# contra1567.net
KiCad netlist of a schematic drawn in EAGLE
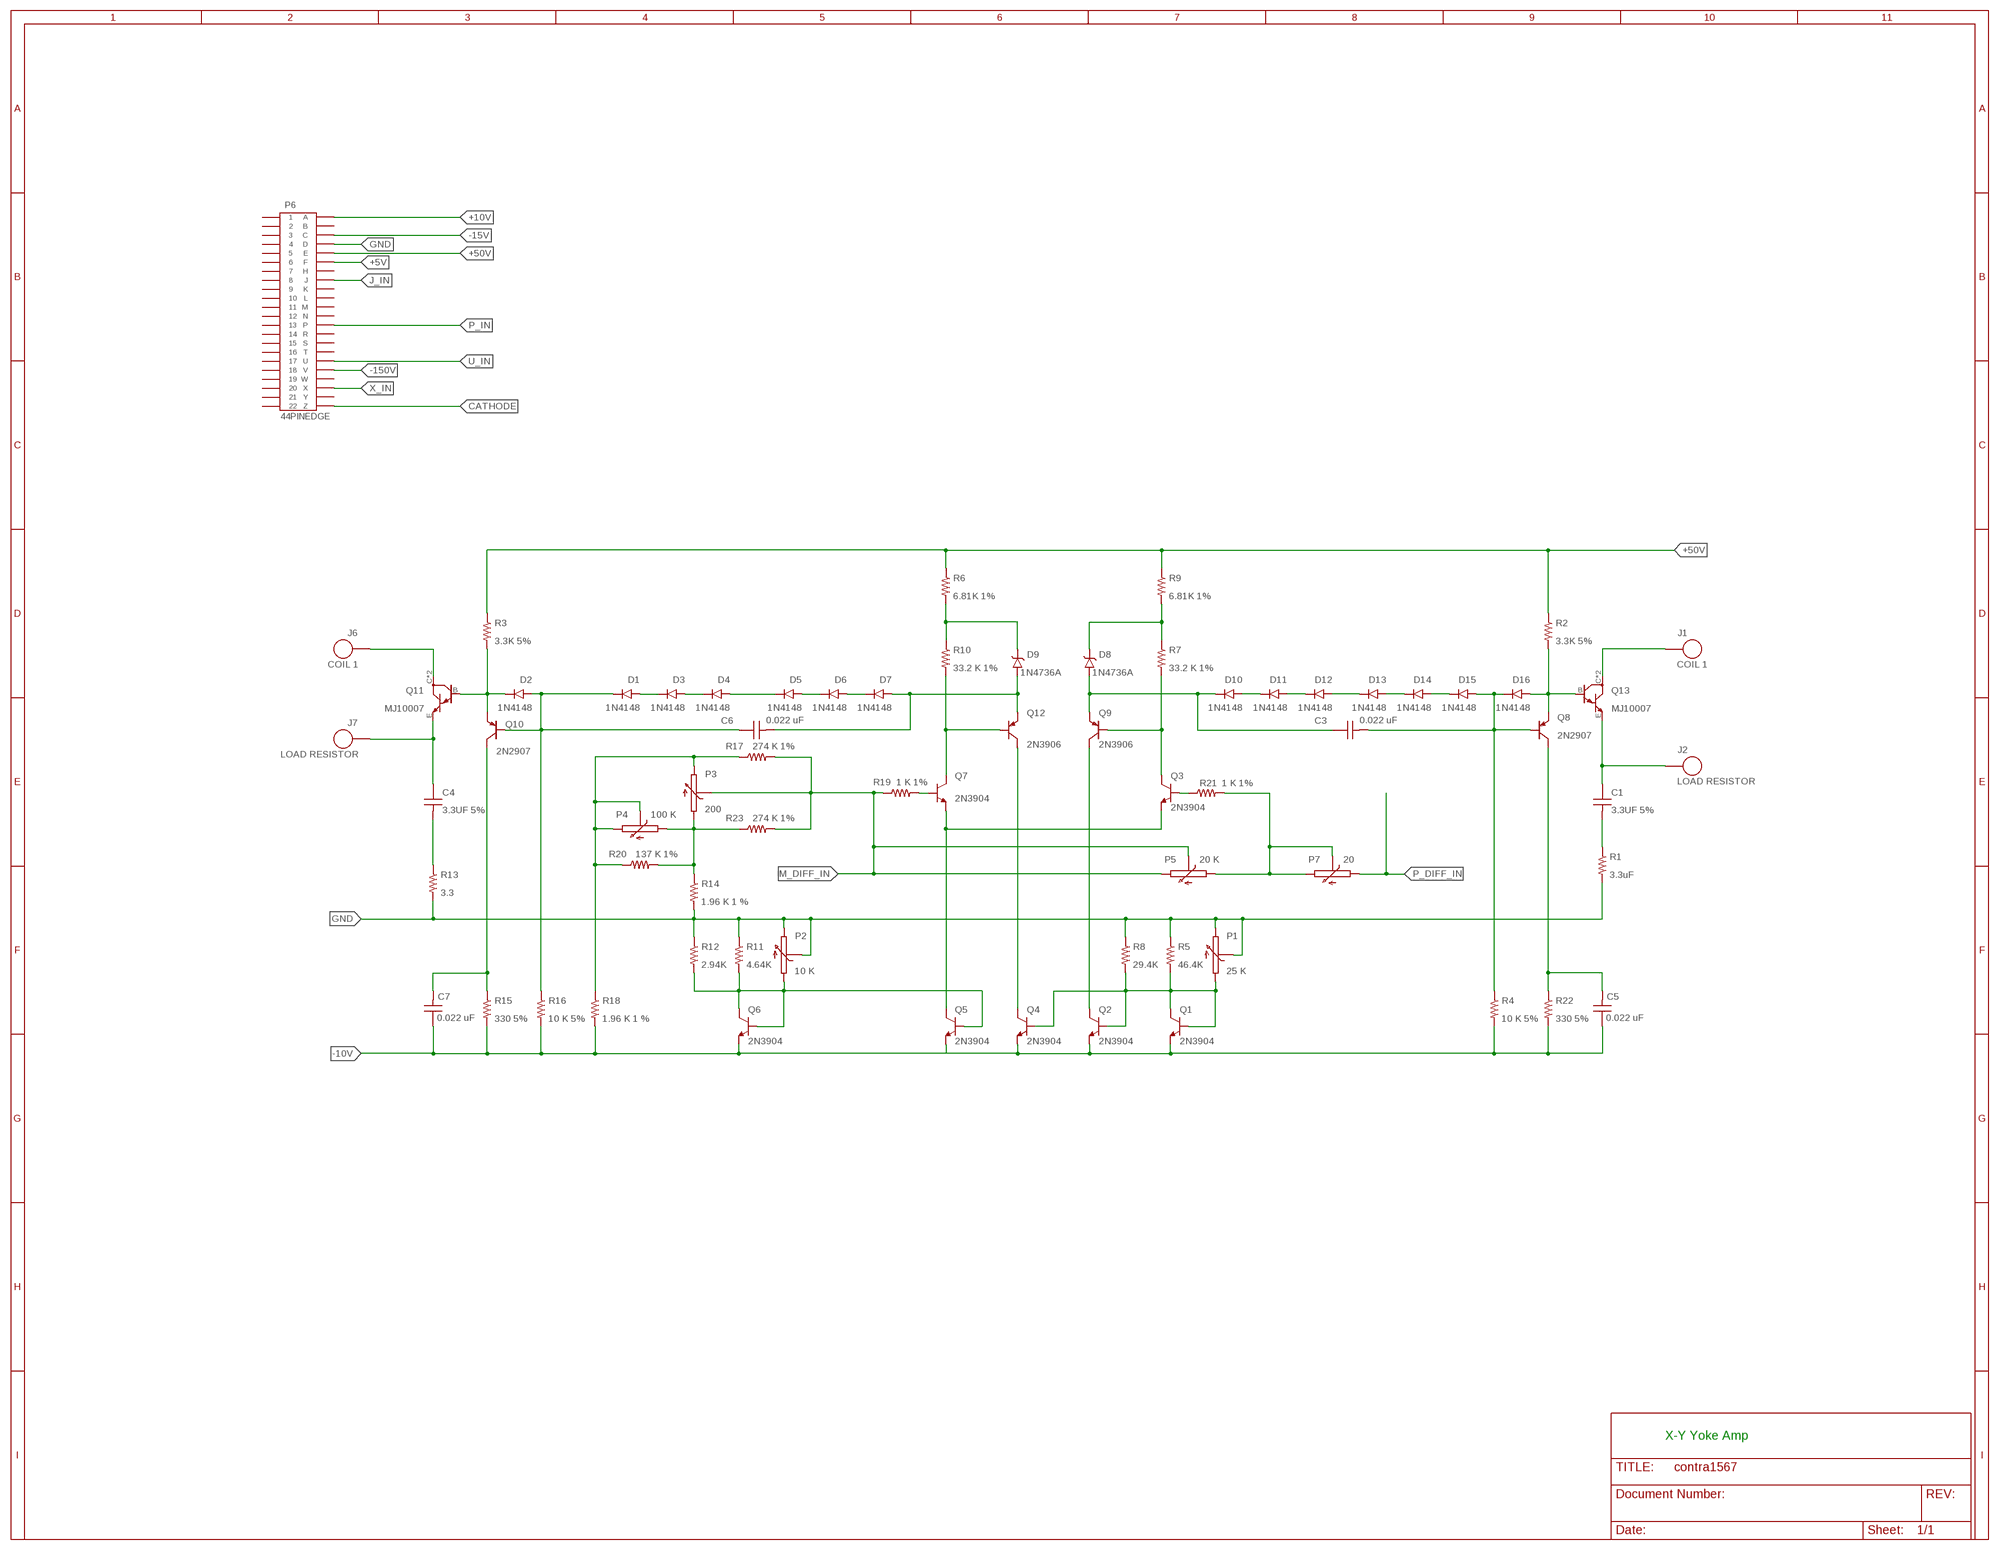
[diagram p0: schematic, sheet 1]

(export (version "E")
  (design (tool "Eeschema 10.0.6"))
  (components
    (comp (ref "C1")
      (value "3.3UF 5%")
      (footprint "eagle-import:CAP-3-PT-ZERO-3UF-250V-FILM")
      (libsource (lib "eagle-import") (part "ECQ-E2335JF"))
    )
    (comp (ref "C3")
      (value "0.022 uF")
      (footprint "eagle-import:CAP-ZERO-PT-ZERO-22UF-250V-FILM")
      (libsource (lib "eagle-import") (part "ECQ-E2223JF"))
    )
    (comp (ref "C4")
      (value "3.3UF 5%")
      (footprint "eagle-import:CAP-3-PT-ZERO-3UF-250V-FILM")
      (libsource (lib "eagle-import") (part "ECQ-E2335JF"))
    )
    (comp (ref "C5")
      (value "0.022 uF")
      (footprint "eagle-import:CAP-ZERO-PT-ZERO-22UF-250V-FILM")
      (libsource (lib "eagle-import") (part "ECQ-E2223JF"))
    )
    (comp (ref "C6")
      (value "0.022 uF")
      (footprint "eagle-import:CAP-ZERO-PT-ZERO-22UF-250V-FILM")
      (libsource (lib "eagle-import") (part "ECQ-E2223JF"))
    )
    (comp (ref "C7")
      (value "0.022 uF")
      (footprint "eagle-import:CAP-ZERO-PT-ZERO-22UF-250V-FILM")
      (libsource (lib "eagle-import") (part "ECQ-E2223JF"))
    )
    (comp (ref "D1")
      (value "1N4148")
      (footprint "eagle-import:DO35-7")
      (libsource (lib "eagle-import") (part "1N4148"))
    )
    (comp (ref "D2")
      (value "1N4148")
      (footprint "eagle-import:DO35-7")
      (libsource (lib "eagle-import") (part "1N4148"))
    )
    (comp (ref "D3")
      (value "1N4148")
      (footprint "eagle-import:DO35-7")
      (libsource (lib "eagle-import") (part "1N4148"))
    )
    (comp (ref "D4")
      (value "1N4148")
      (footprint "eagle-import:DO35-7")
      (libsource (lib "eagle-import") (part "1N4148"))
    )
    (comp (ref "D5")
      (value "1N4148")
      (footprint "eagle-import:DO35-7")
      (libsource (lib "eagle-import") (part "1N4148"))
    )
    (comp (ref "D6")
      (value "1N4148")
      (footprint "eagle-import:DO35-7")
      (libsource (lib "eagle-import") (part "1N4148"))
    )
    (comp (ref "D7")
      (value "1N4148")
      (footprint "eagle-import:DO35-7")
      (libsource (lib "eagle-import") (part "1N4148"))
    )
    (comp (ref "D8")
      (value "1N4736A")
      (footprint "eagle-import:DO41")
      (libsource (lib "eagle-import") (part "1N4736A"))
    )
    (comp (ref "D9")
      (value "1N4736A")
      (footprint "eagle-import:DO41")
      (libsource (lib "eagle-import") (part "1N4736A"))
    )
    (comp (ref "D10")
      (value "1N4148")
      (footprint "eagle-import:DO35-7")
      (libsource (lib "eagle-import") (part "1N4148"))
    )
    (comp (ref "D11")
      (value "1N4148")
      (footprint "eagle-import:DO35-7")
      (libsource (lib "eagle-import") (part "1N4148"))
    )
    (comp (ref "D12")
      (value "1N4148")
      (footprint "eagle-import:DO35-7")
      (libsource (lib "eagle-import") (part "1N4148"))
    )
    (comp (ref "D13")
      (value "1N4148")
      (footprint "eagle-import:DO35-7")
      (libsource (lib "eagle-import") (part "1N4148"))
    )
    (comp (ref "D14")
      (value "1N4148")
      (footprint "eagle-import:DO35-7")
      (libsource (lib "eagle-import") (part "1N4148"))
    )
    (comp (ref "D15")
      (value "1N4148")
      (footprint "eagle-import:DO35-7")
      (libsource (lib "eagle-import") (part "1N4148"))
    )
    (comp (ref "D16")
      (value "1N4148")
      (footprint "eagle-import:DO35-7")
      (libsource (lib "eagle-import") (part "1N4148"))
    )
    (comp (ref "J1")
      (value "COIL 1")
      (footprint "eagle-import:AWG18")
      (libsource (lib "eagle-import") (part "AWG18"))
    )
    (comp (ref "J2")
      (value "LOAD RESISTOR")
      (footprint "eagle-import:AWG18")
      (libsource (lib "eagle-import") (part "AWG18"))
    )
    (comp (ref "J6")
      (value "COIL 1")
      (footprint "eagle-import:AWG18")
      (libsource (lib "eagle-import") (part "AWG18"))
    )
    (comp (ref "J7")
      (value "LOAD RESISTOR")
      (footprint "eagle-import:AWG18")
      (libsource (lib "eagle-import") (part "AWG18"))
    )
    (comp (ref "P1")
      (value "25 K")
      (footprint "eagle-import:3006P")
      (libsource (lib "eagle-import") (part "POT-3006P"))
    )
    (comp (ref "P2")
      (value "10 K")
      (footprint "eagle-import:3006P")
      (libsource (lib "eagle-import") (part "POT-3006P"))
    )
    (comp (ref "P3")
      (value "200")
      (footprint "eagle-import:3006P")
      (libsource (lib "eagle-import") (part "POT-3006P"))
    )
    (comp (ref "P4")
      (value "100 K")
      (footprint "eagle-import:3006P")
      (libsource (lib "eagle-import") (part "POT-3006P"))
    )
    (comp (ref "P5")
      (value "20 K")
      (footprint "eagle-import:3006P")
      (libsource (lib "eagle-import") (part "POT-3006P"))
    )
    (comp (ref "P6")
      (value "44PINEDGE")
      (footprint "eagle-import:44PINEDGE")
      (libsource (lib "eagle-import") (part "44PINEDGE"))
    )
    (comp (ref "P7")
      (value "20")
      (footprint "eagle-import:3006P")
      (libsource (lib "eagle-import") (part "POT-3006P"))
    )
    (comp (ref "Q1")
      (value "2N3904")
      (footprint "eagle-import:TO92")
      (libsource (lib "eagle-import") (part "2N3904"))
    )
    (comp (ref "Q2")
      (value "2N3904")
      (footprint "eagle-import:TO92")
      (libsource (lib "eagle-import") (part "2N3904"))
    )
    (comp (ref "Q3")
      (value "2N3904")
      (footprint "eagle-import:TO92")
      (libsource (lib "eagle-import") (part "2N3904"))
    )
    (comp (ref "Q4")
      (value "2N3904")
      (footprint "eagle-import:TO92")
      (libsource (lib "eagle-import") (part "2N3904"))
    )
    (comp (ref "Q5")
      (value "2N3904")
      (footprint "eagle-import:TO92")
      (libsource (lib "eagle-import") (part "2N3904"))
    )
    (comp (ref "Q6")
      (value "2N3904")
      (footprint "eagle-import:TO92")
      (libsource (lib "eagle-import") (part "2N3904"))
    )
    (comp (ref "Q7")
      (value "2N3904")
      (footprint "eagle-import:TO92")
      (libsource (lib "eagle-import") (part "2N3904"))
    )
    (comp (ref "Q8")
      (value "2N2907")
      (footprint "eagle-import:TO18")
      (libsource (lib "eagle-import") (part "2N2907"))
    )
    (comp (ref "Q9")
      (value "2N3906")
      (footprint "eagle-import:TO92")
      (libsource (lib "eagle-import") (part "2N3906"))
    )
    (comp (ref "Q10")
      (value "2N2907")
      (footprint "eagle-import:TO18")
      (libsource (lib "eagle-import") (part "2N2907"))
    )
    (comp (ref "Q11")
      (value "MJ10007")
      (footprint "eagle-import:TO3")
      (libsource (lib "eagle-import") (part "MJ10007"))
    )
    (comp (ref "Q12")
      (value "2N3906")
      (footprint "eagle-import:TO92")
      (libsource (lib "eagle-import") (part "2N3906"))
    )
    (comp (ref "Q13")
      (value "MJ10007")
      (footprint "eagle-import:TO3")
      (libsource (lib "eagle-import") (part "MJ10007"))
    )
    (comp (ref "R1")
      (value "3.3uF")
      (footprint "eagle-import:R_THREEWATT")
      (libsource (lib "eagle-import") (part "AXIALRESISTORTHREE_WATT"))
    )
    (comp (ref "R2")
      (value "3.3K 5%")
      (footprint "eagle-import:R_TWOWATT")
      (libsource (lib "eagle-import") (part "AXIALRESISTORTWO_WATT"))
    )
    (comp (ref "R3")
      (value "3.3K 5%")
      (footprint "eagle-import:R_TWOWATT")
      (libsource (lib "eagle-import") (part "AXIALRESISTORTWO_WATT"))
    )
    (comp (ref "R4")
      (value "10 K 5%")
      (footprint "eagle-import:R_HALFWATT")
      (libsource (lib "eagle-import") (part "AXIALRESISTORHALF_WATT"))
    )
    (comp (ref "R5")
      (value "46.4K")
      (footprint "eagle-import:R_QUARTERWATT")
      (libsource (lib "eagle-import") (part "AXIALRESISTORQUARTER_WATT"))
    )
    (comp (ref "R6")
      (value "6.81K 1%")
      (footprint "eagle-import:R_HALFWATT")
      (libsource (lib "eagle-import") (part "AXIALRESISTORHALF_WATT"))
    )
    (comp (ref "R7")
      (value "33.2 K 1%")
      (footprint "eagle-import:R_HALFWATT")
      (libsource (lib "eagle-import") (part "AXIALRESISTORHALF_WATT"))
    )
    (comp (ref "R8")
      (value "29.4K")
      (footprint "eagle-import:R_QUARTERWATT")
      (libsource (lib "eagle-import") (part "AXIALRESISTORQUARTER_WATT"))
    )
    (comp (ref "R9")
      (value "6.81K 1%")
      (footprint "eagle-import:R_HALFWATT")
      (libsource (lib "eagle-import") (part "AXIALRESISTORHALF_WATT"))
    )
    (comp (ref "R10")
      (value "33.2 K 1%")
      (footprint "eagle-import:R_HALFWATT")
      (libsource (lib "eagle-import") (part "AXIALRESISTORHALF_WATT"))
    )
    (comp (ref "R11")
      (value "4.64K")
      (footprint "eagle-import:R_QUARTERWATT")
      (libsource (lib "eagle-import") (part "AXIALRESISTORQUARTER_WATT"))
    )
    (comp (ref "R12")
      (value "2.94K")
      (footprint "eagle-import:R_QUARTERWATT")
      (libsource (lib "eagle-import") (part "AXIALRESISTORQUARTER_WATT"))
    )
    (comp (ref "R13")
      (value "3.3")
      (footprint "eagle-import:R_THREEWATT")
      (libsource (lib "eagle-import") (part "AXIALRESISTORTHREE_WATT"))
    )
    (comp (ref "R14")
      (value "1.96 K 1 %")
      (footprint "eagle-import:R_QUARTERWATT")
      (libsource (lib "eagle-import") (part "AXIALRESISTORQUARTER_WATT"))
    )
    (comp (ref "R15")
      (value "330 5%")
      (footprint "eagle-import:R_ONEWATT")
      (libsource (lib "eagle-import") (part "AXIALRESISTORONE_WATT"))
    )
    (comp (ref "R16")
      (value "10 K 5%")
      (footprint "eagle-import:R_HALFWATT")
      (libsource (lib "eagle-import") (part "AXIALRESISTORHALF_WATT"))
    )
    (comp (ref "R17")
      (value "274 K 1%")
      (footprint "eagle-import:R_QUARTERWATT")
      (libsource (lib "eagle-import") (part "AXIALRESISTORQUARTER_WATT"))
    )
    (comp (ref "R18")
      (value "1.96 K 1 %")
      (footprint "eagle-import:R_QUARTERWATT")
      (libsource (lib "eagle-import") (part "AXIALRESISTORQUARTER_WATT"))
    )
    (comp (ref "R19")
      (value "1 K 1%")
      (footprint "eagle-import:R_QUARTERWATT")
      (libsource (lib "eagle-import") (part "AXIALRESISTORQUARTER_WATT"))
    )
    (comp (ref "R20")
      (value "137 K 1%")
      (footprint "eagle-import:R_QUARTERWATT")
      (libsource (lib "eagle-import") (part "AXIALRESISTORQUARTER_WATT"))
    )
    (comp (ref "R21")
      (value "1 K 1%")
      (footprint "eagle-import:R_QUARTERWATT")
      (libsource (lib "eagle-import") (part "AXIALRESISTORQUARTER_WATT"))
    )
    (comp (ref "R22")
      (value "330 5%")
      (footprint "eagle-import:R_ONEWATT")
      (libsource (lib "eagle-import") (part "AXIALRESISTORONE_WATT"))
    )
    (comp (ref "R23")
      (value "274 K 1%")
      (footprint "eagle-import:R_QUARTERWATT")
      (libsource (lib "eagle-import") (part "AXIALRESISTORQUARTER_WATT"))
    )
  )
  (nets
    (net (code "1") (name "+5V") (class "Default")
      (node (ref "P6") (pin "F") (pinfunction "F_F") (pintype "passive"))
    )
    (net (code "2") (name "+10V") (class "Default")
      (node (ref "P6") (pin "A") (pinfunction "A_A") (pintype "passive"))
    )
    (net (code "3") (name "+50V") (class "Default")
      (node (ref "P6") (pin "E") (pinfunction "E_E") (pintype "passive"))
      (node (ref "R2") (pin "1") (pinfunction "P$1_1") (pintype "passive"))
      (node (ref "R3") (pin "1") (pinfunction "P$1_1") (pintype "passive"))
      (node (ref "R6") (pin "1") (pinfunction "P$1_1") (pintype "passive"))
      (node (ref "R9") (pin "1") (pinfunction "P$1_1") (pintype "passive"))
    )
    (net (code "4") (name "-10V") (class "Default")
      (node (ref "C5") (pin "1") (pinfunction "1_1") (pintype "passive"))
      (node (ref "C7") (pin "1") (pinfunction "1_1") (pintype "passive"))
      (node (ref "Q1") (pin "3") (pinfunction "E_3") (pintype "passive"))
      (node (ref "Q2") (pin "3") (pinfunction "E_3") (pintype "passive"))
      (node (ref "Q4") (pin "3") (pinfunction "E_3") (pintype "passive"))
      (node (ref "Q6") (pin "3") (pinfunction "E_3") (pintype "passive"))
      (node (ref "R15") (pin "2") (pinfunction "P$2_2") (pintype "passive"))
      (node (ref "R16") (pin "2") (pinfunction "P$2_2") (pintype "passive"))
      (node (ref "R18") (pin "2") (pinfunction "P$2_2") (pintype "passive"))
      (node (ref "R22") (pin "2") (pinfunction "P$2_2") (pintype "passive"))
      (node (ref "R4") (pin "2") (pinfunction "P$2_2") (pintype "passive"))
    )
    (net (code "5") (name "-15V") (class "Default")
      (node (ref "P6") (pin "C") (pinfunction "C_C") (pintype "passive"))
    )
    (net (code "6") (name "-150V") (class "Default")
      (node (ref "P6") (pin "V") (pinfunction "V_V") (pintype "passive"))
    )
    (net (code "7") (name "CATHODE") (class "Default")
      (node (ref "P6") (pin "Z") (pinfunction "Z_Z") (pintype "passive"))
    )
    (net (code "8") (name "GND") (class "Default")
      (node (ref "P1") (pin "2") (pinfunction "S_2") (pintype "passive"))
      (node (ref "P1") (pin "3") (pinfunction "E_3") (pintype "passive"))
      (node (ref "P2") (pin "2") (pinfunction "S_2") (pintype "passive"))
      (node (ref "P2") (pin "3") (pinfunction "E_3") (pintype "passive"))
      (node (ref "P6") (pin "D") (pinfunction "D_D") (pintype "passive"))
      (node (ref "R1") (pin "2") (pinfunction "P$2_2") (pintype "passive"))
      (node (ref "R11") (pin "1") (pinfunction "P$1_1") (pintype "passive"))
      (node (ref "R12") (pin "1") (pinfunction "P$1_1") (pintype "passive"))
      (node (ref "R13") (pin "2") (pinfunction "P$2_2") (pintype "passive"))
      (node (ref "R14") (pin "2") (pinfunction "P$2_2") (pintype "passive"))
      (node (ref "R5") (pin "1") (pinfunction "P$1_1") (pintype "passive"))
      (node (ref "R8") (pin "1") (pinfunction "P$1_1") (pintype "passive"))
    )
    (net (code "9") (name "J_IN") (class "Default")
      (node (ref "P6") (pin "J") (pinfunction "J_J") (pintype "passive"))
    )
    (net (code "10") (name "M_DIFF_IN") (class "Default")
      (node (ref "P3") (pin "2") (pinfunction "S_2") (pintype "passive"))
      (node (ref "P5") (pin "2") (pinfunction "S_2") (pintype "passive"))
      (node (ref "P5") (pin "3") (pinfunction "E_3") (pintype "passive"))
      (node (ref "R17") (pin "2") (pinfunction "P$2_2") (pintype "passive"))
      (node (ref "R19") (pin "1") (pinfunction "P$1_1") (pintype "passive"))
      (node (ref "R23") (pin "2") (pinfunction "P$2_2") (pintype "passive"))
    )
    (net (code "11") (name "Net-(C1-Pad1)") (class "Default")
      (node (ref "C1") (pin "1") (pinfunction "1_1") (pintype "passive"))
      (node (ref "J2") (pin "P$1") (pinfunction "P$1_P$1") (pintype "bidirectional"))
      (node (ref "Q13") (pin "E") (pinfunction "E_E") (pintype "passive"))
    )
    (net (code "12") (name "Net-(C4-Pad1)") (class "Default")
      (node (ref "C4") (pin "1") (pinfunction "1_1") (pintype "passive"))
      (node (ref "J7") (pin "P$1") (pinfunction "P$1_P$1") (pintype "bidirectional"))
      (node (ref "Q11") (pin "E") (pinfunction "E_E") (pintype "passive"))
    )
    (net (code "13") (name "Net-(D1-PadA)") (class "Default")
      (node (ref "D1") (pin "A") (pinfunction "A_A") (pintype "passive"))
      (node (ref "D3") (pin "C") (pinfunction "C_C") (pintype "passive"))
    )
    (net (code "14") (name "Net-(D3-PadA)") (class "Default")
      (node (ref "D3") (pin "A") (pinfunction "A_A") (pintype "passive"))
      (node (ref "D4") (pin "C") (pinfunction "C_C") (pintype "passive"))
    )
    (net (code "15") (name "Net-(D4-PadA)") (class "Default")
      (node (ref "D4") (pin "A") (pinfunction "A_A") (pintype "passive"))
      (node (ref "D5") (pin "C") (pinfunction "C_C") (pintype "passive"))
    )
    (net (code "16") (name "Net-(D5-PadA)") (class "Default")
      (node (ref "D5") (pin "A") (pinfunction "A_A") (pintype "passive"))
      (node (ref "D6") (pin "C") (pinfunction "C_C") (pintype "passive"))
    )
    (net (code "17") (name "Net-(D6-PadA)") (class "Default")
      (node (ref "D6") (pin "A") (pinfunction "A_A") (pintype "passive"))
      (node (ref "D7") (pin "C") (pinfunction "C_C") (pintype "passive"))
    )
    (net (code "18") (name "Net-(D10-PadA)") (class "Default")
      (node (ref "D10") (pin "A") (pinfunction "A_A") (pintype "passive"))
      (node (ref "D11") (pin "C") (pinfunction "C_C") (pintype "passive"))
    )
    (net (code "19") (name "Net-(D11-PadA)") (class "Default")
      (node (ref "D11") (pin "A") (pinfunction "A_A") (pintype "passive"))
      (node (ref "D12") (pin "C") (pinfunction "C_C") (pintype "passive"))
    )
    (net (code "20") (name "Net-(D12-PadA)") (class "Default")
      (node (ref "D12") (pin "A") (pinfunction "A_A") (pintype "passive"))
      (node (ref "D13") (pin "C") (pinfunction "C_C") (pintype "passive"))
    )
    (net (code "21") (name "Net-(D13-PadA)") (class "Default")
      (node (ref "D13") (pin "A") (pinfunction "A_A") (pintype "passive"))
      (node (ref "D14") (pin "C") (pinfunction "C_C") (pintype "passive"))
    )
    (net (code "22") (name "Net-(D14-PadA)") (class "Default")
      (node (ref "D14") (pin "A") (pinfunction "A_A") (pintype "passive"))
      (node (ref "D15") (pin "C") (pinfunction "C_C") (pintype "passive"))
    )
    (net (code "23") (name "Net-(J1-PadP$1)") (class "Default")
      (node (ref "J1") (pin "P$1") (pinfunction "P$1_P$1") (pintype "bidirectional"))
      (node (ref "Q13") (pin "C") (pinfunction "C_C") (pintype "passive"))
      (node (ref "Q13") (pin "C/") (pinfunction "C_C/") (pintype "passive"))
    )
    (net (code "24") (name "Net-(J6-PadP$1)") (class "Default")
      (node (ref "J6") (pin "P$1") (pinfunction "P$1_P$1") (pintype "bidirectional"))
      (node (ref "Q11") (pin "C") (pinfunction "C_C") (pintype "passive"))
      (node (ref "Q11") (pin "C/") (pinfunction "C_C/") (pintype "passive"))
    )
    (net (code "25") (name "Net-(P1-A)") (class "Default")
      (node (ref "P1") (pin "1") (pinfunction "A_1") (pintype "passive"))
      (node (ref "Q1") (pin "1") (pinfunction "C_1") (pintype "passive"))
      (node (ref "Q1") (pin "2") (pinfunction "B_2") (pintype "passive"))
      (node (ref "Q2") (pin "2") (pinfunction "B_2") (pintype "passive"))
      (node (ref "Q4") (pin "2") (pinfunction "B_2") (pintype "passive"))
      (node (ref "R5") (pin "2") (pinfunction "P$2_2") (pintype "passive"))
      (node (ref "R8") (pin "2") (pinfunction "P$2_2") (pintype "passive"))
    )
    (net (code "26") (name "Net-(P2-A)") (class "Default")
      (node (ref "P2") (pin "1") (pinfunction "A_1") (pintype "passive"))
      (node (ref "Q5") (pin "2") (pinfunction "B_2") (pintype "passive"))
      (node (ref "Q6") (pin "1") (pinfunction "C_1") (pintype "passive"))
      (node (ref "Q6") (pin "2") (pinfunction "B_2") (pintype "passive"))
      (node (ref "R11") (pin "2") (pinfunction "P$2_2") (pintype "passive"))
      (node (ref "R12") (pin "2") (pinfunction "P$2_2") (pintype "passive"))
    )
    (net (code "27") (name "Net-(P3-A)") (class "Default")
      (node (ref "P3") (pin "1") (pinfunction "A_1") (pintype "passive"))
      (node (ref "P4") (pin "1") (pinfunction "A_1") (pintype "passive"))
      (node (ref "R14") (pin "1") (pinfunction "P$1_1") (pintype "passive"))
      (node (ref "R20") (pin "2") (pinfunction "P$2_2") (pintype "passive"))
      (node (ref "R23") (pin "1") (pinfunction "P$1_1") (pintype "passive"))
    )
    (net (code "28") (name "Net-(P3-E)") (class "Default")
      (node (ref "P3") (pin "3") (pinfunction "E_3") (pintype "passive"))
      (node (ref "P4") (pin "2") (pinfunction "S_2") (pintype "passive"))
      (node (ref "P4") (pin "3") (pinfunction "E_3") (pintype "passive"))
      (node (ref "R17") (pin "1") (pinfunction "P$1_1") (pintype "passive"))
      (node (ref "R18") (pin "1") (pinfunction "P$1_1") (pintype "passive"))
      (node (ref "R20") (pin "1") (pinfunction "P$1_1") (pintype "passive"))
    )
    (net (code "29") (name "Net-(P5-A)") (class "Default")
      (node (ref "P5") (pin "1") (pinfunction "A_1") (pintype "passive"))
      (node (ref "P7") (pin "2") (pinfunction "S_2") (pintype "passive"))
      (node (ref "P7") (pin "3") (pinfunction "E_3") (pintype "passive"))
      (node (ref "R21") (pin "2") (pinfunction "P$2_2") (pintype "passive"))
    )
    (net (code "30") (name "Net-(Q2-C)") (class "Default")
      (node (ref "Q2") (pin "1") (pinfunction "C_1") (pintype "passive"))
      (node (ref "Q9") (pin "1") (pinfunction "C_1") (pintype "passive"))
    )
    (net (code "31") (name "Net-(Q3-B)") (class "Default")
      (node (ref "Q3") (pin "2") (pinfunction "B_2") (pintype "passive"))
      (node (ref "R21") (pin "1") (pinfunction "P$1_1") (pintype "passive"))
    )
    (net (code "32") (name "Net-(Q3-C)") (class "Default")
      (node (ref "Q3") (pin "1") (pinfunction "C_1") (pintype "passive"))
      (node (ref "Q9") (pin "2") (pinfunction "B_2") (pintype "passive"))
      (node (ref "R7") (pin "2") (pinfunction "P$2_2") (pintype "passive"))
    )
    (net (code "33") (name "Net-(Q3-E)") (class "Default")
      (node (ref "Q3") (pin "3") (pinfunction "E_3") (pintype "passive"))
      (node (ref "Q5") (pin "1") (pinfunction "C_1") (pintype "passive"))
      (node (ref "Q7") (pin "3") (pinfunction "E_3") (pintype "passive"))
    )
    (net (code "34") (name "Net-(Q7-B)") (class "Default")
      (node (ref "Q7") (pin "2") (pinfunction "B_2") (pintype "passive"))
      (node (ref "R19") (pin "2") (pinfunction "P$2_2") (pintype "passive"))
    )
    (net (code "35") (name "Net-(Q8-B)") (class "Default")
      (node (ref "C3") (pin "2") (pinfunction "2_2") (pintype "passive"))
      (node (ref "D15") (pin "A") (pinfunction "A_A") (pintype "passive"))
      (node (ref "D16") (pin "C") (pinfunction "C_C") (pintype "passive"))
      (node (ref "Q8") (pin "2") (pinfunction "B_2") (pintype "passive"))
      (node (ref "R4") (pin "1") (pinfunction "P$1_1") (pintype "passive"))
    )
    (net (code "36") (name "Net-(Q8-C)") (class "Default")
      (node (ref "C5") (pin "2") (pinfunction "2_2") (pintype "passive"))
      (node (ref "Q8") (pin "3") (pinfunction "C_3") (pintype "passive"))
      (node (ref "R22") (pin "1") (pinfunction "P$1_1") (pintype "passive"))
    )
    (net (code "37") (name "Net-(Q8-E)") (class "Default")
      (node (ref "D16") (pin "A") (pinfunction "A_A") (pintype "passive"))
      (node (ref "Q13") (pin "B") (pinfunction "B_B") (pintype "passive"))
      (node (ref "Q8") (pin "1") (pinfunction "E_1") (pintype "passive"))
      (node (ref "R2") (pin "2") (pinfunction "P$2_2") (pintype "passive"))
    )
    (net (code "38") (name "Net-(Q9-E)") (class "Default")
      (node (ref "C3") (pin "1") (pinfunction "1_1") (pintype "passive"))
      (node (ref "D10") (pin "C") (pinfunction "C_C") (pintype "passive"))
      (node (ref "D8") (pin "A") (pinfunction "A_A") (pintype "passive"))
      (node (ref "Q9") (pin "3") (pinfunction "E_3") (pintype "passive"))
    )
    (net (code "39") (name "Net-(Q10-B)") (class "Default")
      (node (ref "C6") (pin "1") (pinfunction "1_1") (pintype "passive"))
      (node (ref "D1") (pin "C") (pinfunction "C_C") (pintype "passive"))
      (node (ref "D2") (pin "A") (pinfunction "A_A") (pintype "passive"))
      (node (ref "Q10") (pin "2") (pinfunction "B_2") (pintype "passive"))
      (node (ref "R16") (pin "1") (pinfunction "P$1_1") (pintype "passive"))
    )
    (net (code "40") (name "Net-(Q10-C)") (class "Default")
      (node (ref "C7") (pin "2") (pinfunction "2_2") (pintype "passive"))
      (node (ref "Q10") (pin "3") (pinfunction "C_3") (pintype "passive"))
      (node (ref "R15") (pin "1") (pinfunction "P$1_1") (pintype "passive"))
    )
    (net (code "41") (name "Net-(Q10-E)") (class "Default")
      (node (ref "D2") (pin "C") (pinfunction "C_C") (pintype "passive"))
      (node (ref "Q10") (pin "1") (pinfunction "E_1") (pintype "passive"))
      (node (ref "Q11") (pin "B") (pinfunction "B_B") (pintype "passive"))
      (node (ref "R3") (pin "2") (pinfunction "P$2_2") (pintype "passive"))
    )
    (net (code "42") (name "Net-(Q12-B)") (class "Default")
      (node (ref "Q12") (pin "2") (pinfunction "B_2") (pintype "passive"))
      (node (ref "Q7") (pin "1") (pinfunction "C_1") (pintype "passive"))
      (node (ref "R10") (pin "2") (pinfunction "P$2_2") (pintype "passive"))
    )
    (net (code "43") (name "Net-(Q12-C)") (class "Default")
      (node (ref "Q12") (pin "1") (pinfunction "C_1") (pintype "passive"))
      (node (ref "Q4") (pin "1") (pinfunction "C_1") (pintype "passive"))
    )
    (net (code "44") (name "Net-(Q12-E)") (class "Default")
      (node (ref "C6") (pin "2") (pinfunction "2_2") (pintype "passive"))
      (node (ref "D7") (pin "A") (pinfunction "A_A") (pintype "passive"))
      (node (ref "D9") (pin "A") (pinfunction "A_A") (pintype "passive"))
      (node (ref "Q12") (pin "3") (pinfunction "E_3") (pintype "passive"))
    )
    (net (code "45") (name "Net-(R1-P$1)") (class "Default")
      (node (ref "C1") (pin "2") (pinfunction "2_2") (pintype "passive"))
      (node (ref "R1") (pin "1") (pinfunction "P$1_1") (pintype "passive"))
    )
    (net (code "46") (name "Net-(R7-P$1)") (class "Default")
      (node (ref "D8") (pin "C") (pinfunction "C_C") (pintype "passive"))
      (node (ref "R7") (pin "1") (pinfunction "P$1_1") (pintype "passive"))
      (node (ref "R9") (pin "2") (pinfunction "P$2_2") (pintype "passive"))
    )
    (net (code "47") (name "Net-(R10-P$1)") (class "Default")
      (node (ref "D9") (pin "C") (pinfunction "C_C") (pintype "passive"))
      (node (ref "R10") (pin "1") (pinfunction "P$1_1") (pintype "passive"))
      (node (ref "R6") (pin "2") (pinfunction "P$2_2") (pintype "passive"))
    )
    (net (code "48") (name "Net-(R13-P$1)") (class "Default")
      (node (ref "C4") (pin "2") (pinfunction "2_2") (pintype "passive"))
      (node (ref "R13") (pin "1") (pinfunction "P$1_1") (pintype "passive"))
    )
    (net (code "49") (name "P_DIFF_IN") (class "Default")
      (node (ref "P7") (pin "1") (pinfunction "A_1") (pintype "passive"))
    )
    (net (code "50") (name "P_IN") (class "Default")
      (node (ref "P6") (pin "P") (pinfunction "P_P") (pintype "passive"))
    )
    (net (code "51") (name "U_IN") (class "Default")
      (node (ref "P6") (pin "U") (pinfunction "U_U") (pintype "passive"))
    )
    (net (code "52") (name "X_IN") (class "Default")
      (node (ref "P6") (pin "X") (pinfunction "X_X") (pintype "passive"))
    )
    (net (code "53") (name "unconnected-(P6-Pad1)") (class "Default")
      (node (ref "P6") (pin "1") (pinfunction "1_1") (pintype "passive"))
    )
    (net (code "54") (name "unconnected-(P6-Pad2)") (class "Default")
      (node (ref "P6") (pin "2") (pinfunction "2_2") (pintype "passive"))
    )
    (net (code "55") (name "unconnected-(P6-Pad3)") (class "Default")
      (node (ref "P6") (pin "3") (pinfunction "3_3") (pintype "passive"))
    )
    (net (code "56") (name "unconnected-(P6-Pad4)") (class "Default")
      (node (ref "P6") (pin "4") (pinfunction "4_4") (pintype "passive"))
    )
    (net (code "57") (name "unconnected-(P6-Pad5)") (class "Default")
      (node (ref "P6") (pin "5") (pinfunction "5_5") (pintype "passive"))
    )
    (net (code "58") (name "unconnected-(P6-Pad6)") (class "Default")
      (node (ref "P6") (pin "6") (pinfunction "6_6") (pintype "passive"))
    )
    (net (code "59") (name "unconnected-(P6-Pad7)") (class "Default")
      (node (ref "P6") (pin "7") (pinfunction "7_7") (pintype "passive"))
    )
    (net (code "60") (name "unconnected-(P6-Pad8)") (class "Default")
      (node (ref "P6") (pin "8") (pinfunction "8_8") (pintype "passive"))
    )
    (net (code "61") (name "unconnected-(P6-Pad9)") (class "Default")
      (node (ref "P6") (pin "9") (pinfunction "9_9") (pintype "passive"))
    )
    (net (code "62") (name "unconnected-(P6-Pad10)") (class "Default")
      (node (ref "P6") (pin "10") (pinfunction "10_10") (pintype "passive"))
    )
    (net (code "63") (name "unconnected-(P6-Pad11)") (class "Default")
      (node (ref "P6") (pin "11") (pinfunction "11_11") (pintype "passive"))
    )
    (net (code "64") (name "unconnected-(P6-Pad12)") (class "Default")
      (node (ref "P6") (pin "12") (pinfunction "12_12") (pintype "passive"))
    )
    (net (code "65") (name "unconnected-(P6-Pad13)") (class "Default")
      (node (ref "P6") (pin "13") (pinfunction "13_13") (pintype "passive"))
    )
    (net (code "66") (name "unconnected-(P6-Pad14)") (class "Default")
      (node (ref "P6") (pin "14") (pinfunction "14_14") (pintype "passive"))
    )
    (net (code "67") (name "unconnected-(P6-Pad15)") (class "Default")
      (node (ref "P6") (pin "15") (pinfunction "15_15") (pintype "passive"))
    )
    (net (code "68") (name "unconnected-(P6-Pad16)") (class "Default")
      (node (ref "P6") (pin "16") (pinfunction "16_16") (pintype "passive"))
    )
    (net (code "69") (name "unconnected-(P6-Pad17)") (class "Default")
      (node (ref "P6") (pin "17") (pinfunction "17_17") (pintype "passive"))
    )
    (net (code "70") (name "unconnected-(P6-Pad18)") (class "Default")
      (node (ref "P6") (pin "18") (pinfunction "18_18") (pintype "passive"))
    )
    (net (code "71") (name "unconnected-(P6-Pad19)") (class "Default")
      (node (ref "P6") (pin "19") (pinfunction "19_19") (pintype "passive"))
    )
    (net (code "72") (name "unconnected-(P6-Pad20)") (class "Default")
      (node (ref "P6") (pin "20") (pinfunction "20_20") (pintype "passive"))
    )
    (net (code "73") (name "unconnected-(P6-Pad21)") (class "Default")
      (node (ref "P6") (pin "21") (pinfunction "21_21") (pintype "passive"))
    )
    (net (code "74") (name "unconnected-(P6-Pad22)") (class "Default")
      (node (ref "P6") (pin "22") (pinfunction "22_22") (pintype "passive"))
    )
    (net (code "75") (name "unconnected-(P6-PadB)") (class "Default")
      (node (ref "P6") (pin "B") (pinfunction "B_B") (pintype "passive"))
    )
    (net (code "76") (name "unconnected-(P6-PadH)") (class "Default")
      (node (ref "P6") (pin "H") (pinfunction "H_H") (pintype "passive"))
    )
    (net (code "77") (name "unconnected-(P6-PadK)") (class "Default")
      (node (ref "P6") (pin "K") (pinfunction "K_K") (pintype "passive"))
    )
    (net (code "78") (name "unconnected-(P6-PadL)") (class "Default")
      (node (ref "P6") (pin "L") (pinfunction "L_L") (pintype "passive"))
    )
    (net (code "79") (name "unconnected-(P6-PadM)") (class "Default")
      (node (ref "P6") (pin "M") (pinfunction "M_M") (pintype "passive"))
    )
    (net (code "80") (name "unconnected-(P6-PadN)") (class "Default")
      (node (ref "P6") (pin "N") (pinfunction "N_N") (pintype "passive"))
    )
    (net (code "81") (name "unconnected-(P6-PadR)") (class "Default")
      (node (ref "P6") (pin "R") (pinfunction "R_R") (pintype "passive"))
    )
    (net (code "82") (name "unconnected-(P6-PadS)") (class "Default")
      (node (ref "P6") (pin "S") (pinfunction "S_S") (pintype "passive"))
    )
    (net (code "83") (name "unconnected-(P6-PadT)") (class "Default")
      (node (ref "P6") (pin "T") (pinfunction "T_T") (pintype "passive"))
    )
    (net (code "84") (name "unconnected-(P6-PadW)") (class "Default")
      (node (ref "P6") (pin "W") (pinfunction "W_W") (pintype "passive"))
    )
    (net (code "85") (name "unconnected-(P6-PadY)") (class "Default")
      (node (ref "P6") (pin "Y") (pinfunction "Y_Y") (pintype "passive"))
    )
    (net (code "86") (name "unconnected-(Q5-E-Pad3)") (class "Default")
      (node (ref "Q5") (pin "3") (pinfunction "E_3") (pintype "passive"))
    )
  )
)
